# Input_stage.net
KiCad netlist of a schematic drawn in Altium Designer
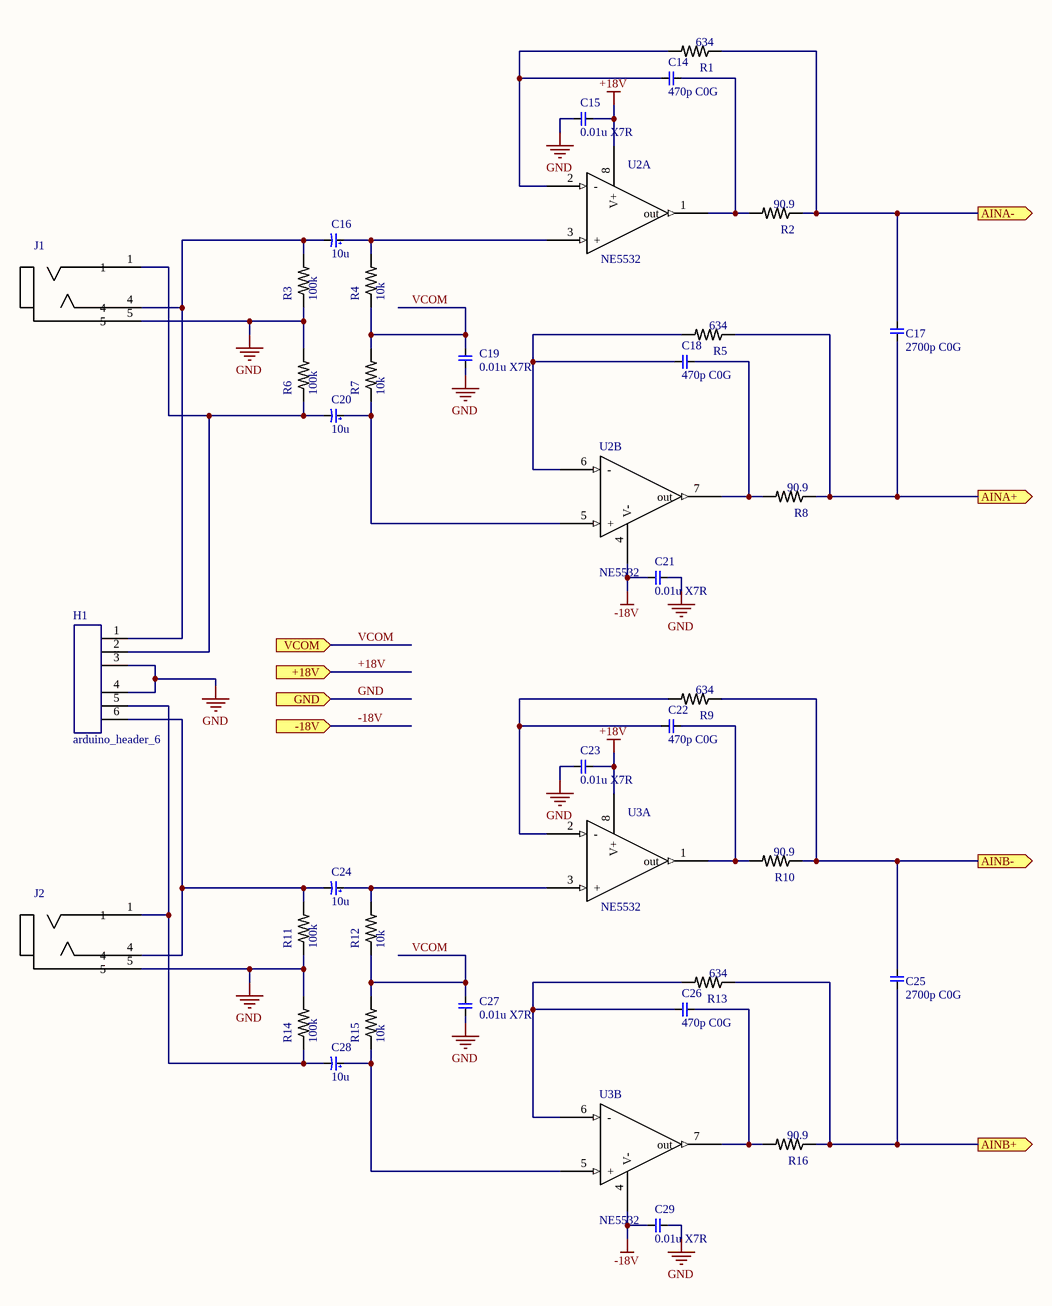
[diagram p0: Input_stage.SchDoc]

(export (version "E")
  (design (tool "Eeschema 10.0.6"))
  (components
    (comp (ref "C14") (value "470p C0G") (footprint "0805_cap") (libsource (lib "Codec_board") (part "Cap")))
    (comp (ref "C15") (value "0.01u X7R") (footprint "0805_cap") (libsource (lib "Codec_board") (part "Cap")))
    (comp (ref "C16")
      (value "10u")
      (footprint "cap 4x5.4")
      (libsource (lib "Codec_board") (part "Cap_electrolytic"))
    )
    (comp (ref "C17") (value "2700p C0G") (footprint "0805_cap") (libsource (lib "Codec_board") (part "Cap")))
    (comp (ref "C18") (value "470p C0G") (footprint "0805_cap") (libsource (lib "Codec_board") (part "Cap")))
    (comp (ref "C19") (value "0.01u X7R") (footprint "0805_cap") (libsource (lib "Codec_board") (part "Cap")))
    (comp (ref "C20")
      (value "10u")
      (footprint "cap 4x5.4")
      (libsource (lib "Codec_board") (part "Cap_electrolytic"))
    )
    (comp (ref "C21") (value "0.01u X7R") (footprint "0805_cap") (libsource (lib "Codec_board") (part "Cap")))
    (comp (ref "C22") (value "470p C0G") (footprint "0805_cap") (libsource (lib "Codec_board") (part "Cap")))
    (comp (ref "C23") (value "0.01u X7R") (footprint "0805_cap") (libsource (lib "Codec_board") (part "Cap")))
    (comp (ref "C24")
      (value "10u")
      (footprint "cap 4x5.4")
      (libsource (lib "Codec_board") (part "Cap_electrolytic"))
    )
    (comp (ref "C25") (value "2700p C0G") (footprint "0805_cap") (libsource (lib "Codec_board") (part "Cap")))
    (comp (ref "C26") (value "470p C0G") (footprint "0805_cap") (libsource (lib "Codec_board") (part "Cap")))
    (comp (ref "C27") (value "0.01u X7R") (footprint "0805_cap") (libsource (lib "Codec_board") (part "Cap")))
    (comp (ref "C28")
      (value "10u")
      (footprint "cap 4x5.4")
      (libsource (lib "Codec_board") (part "Cap_electrolytic"))
    )
    (comp (ref "C29") (value "0.01u X7R") (footprint "0805_cap") (libsource (lib "Codec_board") (part "Cap")))
    (comp (ref "H1")
      (value "arduino_header_6")
      (footprint "header-6_male")
      (libsource (lib "Codec_board") (part "arduino_header_6"))
    )
    (comp (ref "J1")
      (value "35RASMT2BHNTRX")
      (footprint "SWITCHCRAFT_35RASMT2BHNTRX")
      (description "Conn 3.5MM Stereo Jack F 3 POS Solder RA SMD 3 Terminal 1 Port T/R")
      (fields (field (name "MF") "Switchcraft"))
      (libsource (lib "Codec_board") (part "3.5mm jack stereo smd"))
    )
    (comp (ref "J2")
      (value "35RASMT2BHNTRX")
      (footprint "SWITCHCRAFT_35RASMT2BHNTRX")
      (description "Conn 3.5MM Stereo Jack F 3 POS Solder RA SMD 3 Terminal 1 Port T/R")
      (fields (field (name "MF") "Switchcraft"))
      (libsource (lib "Codec_board") (part "3.5mm jack stereo smd"))
    )
    (comp (ref "R1")
      (value "634")
      (footprint "0805")
      (description "RES SMD  1/8W 0805")
      (fields (field (name "MF") "Yageo") (field (name "MP") "AC0805JR-070RL"))
      (libsource (lib "Codec_board") (part "res my"))
    )
    (comp (ref "R2")
      (value "90.9")
      (footprint "0805")
      (description "RES SMD  1/8W 0805")
      (fields (field (name "MF") "Yageo") (field (name "MP") "AC0805JR-070RL"))
      (libsource (lib "Codec_board") (part "res my"))
    )
    (comp (ref "R3")
      (value "100k")
      (footprint "0805")
      (description "RES SMD  1/8W 0805")
      (fields (field (name "MF") "Yageo") (field (name "MP") "AC0805JR-070RL"))
      (libsource (lib "Codec_board") (part "res my"))
    )
    (comp (ref "R4")
      (value "10k")
      (footprint "0805")
      (description "RES SMD  1/8W 0805")
      (fields (field (name "MF") "Yageo") (field (name "MP") "AC0805JR-070RL"))
      (libsource (lib "Codec_board") (part "res my"))
    )
    (comp (ref "R5")
      (value "634")
      (footprint "0805")
      (description "RES SMD  1/8W 0805")
      (fields (field (name "MF") "Yageo") (field (name "MP") "AC0805JR-070RL"))
      (libsource (lib "Codec_board") (part "res my"))
    )
    (comp (ref "R6")
      (value "100k")
      (footprint "0805")
      (description "RES SMD  1/8W 0805")
      (fields (field (name "MF") "Yageo") (field (name "MP") "AC0805JR-070RL"))
      (libsource (lib "Codec_board") (part "res my"))
    )
    (comp (ref "R7")
      (value "10k")
      (footprint "0805")
      (description "RES SMD  1/8W 0805")
      (fields (field (name "MF") "Yageo") (field (name "MP") "AC0805JR-070RL"))
      (libsource (lib "Codec_board") (part "res my"))
    )
    (comp (ref "R8")
      (value "90.9")
      (footprint "0805")
      (description "RES SMD  1/8W 0805")
      (fields (field (name "MF") "Yageo") (field (name "MP") "AC0805JR-070RL"))
      (libsource (lib "Codec_board") (part "res my"))
    )
    (comp (ref "R9")
      (value "634")
      (footprint "0805")
      (description "RES SMD  1/8W 0805")
      (fields (field (name "MF") "Yageo") (field (name "MP") "AC0805JR-070RL"))
      (libsource (lib "Codec_board") (part "res my"))
    )
    (comp (ref "R10")
      (value "90.9")
      (footprint "0805")
      (description "RES SMD  1/8W 0805")
      (fields (field (name "MF") "Yageo") (field (name "MP") "AC0805JR-070RL"))
      (libsource (lib "Codec_board") (part "res my"))
    )
    (comp (ref "R11")
      (value "100k")
      (footprint "0805")
      (description "RES SMD  1/8W 0805")
      (fields (field (name "MF") "Yageo") (field (name "MP") "AC0805JR-070RL"))
      (libsource (lib "Codec_board") (part "res my"))
    )
    (comp (ref "R12")
      (value "10k")
      (footprint "0805")
      (description "RES SMD  1/8W 0805")
      (fields (field (name "MF") "Yageo") (field (name "MP") "AC0805JR-070RL"))
      (libsource (lib "Codec_board") (part "res my"))
    )
    (comp (ref "R13")
      (value "634")
      (footprint "0805")
      (description "RES SMD  1/8W 0805")
      (fields (field (name "MF") "Yageo") (field (name "MP") "AC0805JR-070RL"))
      (libsource (lib "Codec_board") (part "res my"))
    )
    (comp (ref "R14")
      (value "100k")
      (footprint "0805")
      (description "RES SMD  1/8W 0805")
      (fields (field (name "MF") "Yageo") (field (name "MP") "AC0805JR-070RL"))
      (libsource (lib "Codec_board") (part "res my"))
    )
    (comp (ref "R15")
      (value "10k")
      (footprint "0805")
      (description "RES SMD  1/8W 0805")
      (fields (field (name "MF") "Yageo") (field (name "MP") "AC0805JR-070RL"))
      (libsource (lib "Codec_board") (part "res my"))
    )
    (comp (ref "R16")
      (value "90.9")
      (footprint "0805")
      (description "RES SMD  1/8W 0805")
      (fields (field (name "MF") "Yageo") (field (name "MP") "AC0805JR-070RL"))
      (libsource (lib "Codec_board") (part "res my"))
    )
    (comp (ref "U2") (value "NE5532") (footprint "SOIC-8") (libsource (lib "Codec_board") (part "OPA2277")))
    (comp (ref "U3") (value "NE5532") (footprint "SOIC-8") (libsource (lib "Codec_board") (part "OPA2277")))
  )
  (nets
    (net (code "1") (name "+18V") (class "Default")
      (node (ref "C15") (pin "2") (pinfunction "2_2") (pintype "passive"))
      (node (ref "C23") (pin "2") (pinfunction "2_2") (pintype "passive"))
      (node (ref "U2") (pin "8") (pinfunction "V+_8") (pintype "passive"))
      (node (ref "U3") (pin "8") (pinfunction "V+_8") (pintype "passive"))
    )
    (net (code "2") (name "-18V") (class "Default")
      (node (ref "C21") (pin "2") (pinfunction "2_2") (pintype "passive"))
      (node (ref "C29") (pin "2") (pinfunction "2_2") (pintype "passive"))
      (node (ref "U2") (pin "4") (pinfunction "V-_4") (pintype "passive"))
      (node (ref "U3") (pin "4") (pinfunction "V-_4") (pintype "passive"))
    )
    (net (code "3") (name "/AINA+") (class "Default")
      (node (ref "C17") (pin "2") (pinfunction "2_2") (pintype "passive"))
      (node (ref "R5") (pin "1") (pinfunction "1_1") (pintype "passive"))
      (node (ref "R8") (pin "1") (pinfunction "1_1") (pintype "passive"))
    )
    (net (code "4") (name "/AINA-") (class "Default")
      (node (ref "C17") (pin "1") (pinfunction "1_1") (pintype "passive"))
      (node (ref "R1") (pin "1") (pinfunction "1_1") (pintype "passive"))
      (node (ref "R2") (pin "1") (pinfunction "1_1") (pintype "passive"))
    )
    (net (code "5") (name "/AINB+") (class "Default")
      (node (ref "C25") (pin "2") (pinfunction "2_2") (pintype "passive"))
      (node (ref "R13") (pin "1") (pinfunction "1_1") (pintype "passive"))
      (node (ref "R16") (pin "1") (pinfunction "1_1") (pintype "passive"))
    )
    (net (code "6") (name "/AINB-") (class "Default")
      (node (ref "C25") (pin "1") (pinfunction "1_1") (pintype "passive"))
      (node (ref "R10") (pin "1") (pinfunction "1_1") (pintype "passive"))
      (node (ref "R9") (pin "1") (pinfunction "1_1") (pintype "passive"))
    )
    (net (code "7") (name "/VCOM") (class "Default")
      (node (ref "C19") (pin "2") (pinfunction "2_2") (pintype "passive"))
      (node (ref "C27") (pin "2") (pinfunction "2_2") (pintype "passive"))
      (node (ref "R12") (pin "1") (pinfunction "1_1") (pintype "passive"))
      (node (ref "R15") (pin "2") (pinfunction "2_2") (pintype "passive"))
      (node (ref "R4") (pin "1") (pinfunction "1_1") (pintype "passive"))
      (node (ref "R7") (pin "2") (pinfunction "2_2") (pintype "passive"))
    )
    (net (code "8") (name "GND") (class "Default")
      (node (ref "C15") (pin "1") (pinfunction "1_1") (pintype "passive"))
      (node (ref "C19") (pin "1") (pinfunction "1_1") (pintype "passive"))
      (node (ref "C21") (pin "1") (pinfunction "1_1") (pintype "passive"))
      (node (ref "C23") (pin "1") (pinfunction "1_1") (pintype "passive"))
      (node (ref "C27") (pin "1") (pinfunction "1_1") (pintype "passive"))
      (node (ref "C29") (pin "1") (pinfunction "1_1") (pintype "passive"))
      (node (ref "H1") (pin "3") (pinfunction "3_3") (pintype "passive"))
      (node (ref "H1") (pin "4") (pinfunction "4_4") (pintype "passive"))
      (node (ref "J1") (pin "5") (pinfunction "5_5") (pintype "passive"))
      (node (ref "J2") (pin "5") (pinfunction "5_5") (pintype "passive"))
      (node (ref "R11") (pin "1") (pinfunction "1_1") (pintype "passive"))
      (node (ref "R14") (pin "2") (pinfunction "2_2") (pintype "passive"))
      (node (ref "R3") (pin "1") (pinfunction "1_1") (pintype "passive"))
      (node (ref "R6") (pin "2") (pinfunction "2_2") (pintype "passive"))
    )
    (net (code "9") (name "Net-(C16-Pad2)") (class "Default")
      (node (ref "C16") (pin "2") (pinfunction "2_2") (pintype "passive"))
      (node (ref "H1") (pin "1") (pinfunction "1_1") (pintype "passive"))
      (node (ref "J1") (pin "4") (pinfunction "4_4") (pintype "passive"))
      (node (ref "R3") (pin "2") (pinfunction "2_2") (pintype "passive"))
    )
    (net (code "10") (name "Net-(C20-Pad2)") (class "Default")
      (node (ref "C20") (pin "2") (pinfunction "2_2") (pintype "passive"))
      (node (ref "H1") (pin "2") (pinfunction "2_2") (pintype "passive"))
      (node (ref "J1") (pin "1") (pinfunction "1_1") (pintype "passive"))
      (node (ref "R6") (pin "1") (pinfunction "1_1") (pintype "passive"))
    )
    (net (code "11") (name "Net-(C24-Pad2)") (class "Default")
      (node (ref "C24") (pin "2") (pinfunction "2_2") (pintype "passive"))
      (node (ref "H1") (pin "6") (pinfunction "6_6") (pintype "passive"))
      (node (ref "J2") (pin "4") (pinfunction "4_4") (pintype "passive"))
      (node (ref "R11") (pin "2") (pinfunction "2_2") (pintype "passive"))
    )
    (net (code "12") (name "Net-(C28-Pad2)") (class "Default")
      (node (ref "C28") (pin "2") (pinfunction "2_2") (pintype "passive"))
      (node (ref "H1") (pin "5") (pinfunction "5_5") (pintype "passive"))
      (node (ref "J2") (pin "1") (pinfunction "1_1") (pintype "passive"))
      (node (ref "R14") (pin "1") (pinfunction "1_1") (pintype "passive"))
    )
    (net (code "13") (name "Net-(U2A-+)") (class "Default")
      (node (ref "C16") (pin "1") (pinfunction "1_1") (pintype "passive"))
      (node (ref "R4") (pin "2") (pinfunction "2_2") (pintype "passive"))
      (node (ref "U2") (pin "3") (pinfunction "+_3") (pintype "input"))
    )
    (net (code "14") (name "Net-(U2A--)") (class "Default")
      (node (ref "C14") (pin "2") (pinfunction "2_2") (pintype "passive"))
      (node (ref "R1") (pin "2") (pinfunction "2_2") (pintype "passive"))
      (node (ref "U2") (pin "2") (pinfunction "-_2") (pintype "input"))
    )
    (net (code "15") (name "Net-(U2A-out)") (class "Default")
      (node (ref "C14") (pin "1") (pinfunction "1_1") (pintype "passive"))
      (node (ref "R2") (pin "2") (pinfunction "2_2") (pintype "passive"))
      (node (ref "U2") (pin "1") (pinfunction "out_1") (pintype "output"))
    )
    (net (code "16") (name "Net-(U2B-+)") (class "Default")
      (node (ref "C20") (pin "1") (pinfunction "1_1") (pintype "passive"))
      (node (ref "R7") (pin "1") (pinfunction "1_1") (pintype "passive"))
      (node (ref "U2") (pin "5") (pinfunction "+_5") (pintype "input"))
    )
    (net (code "17") (name "Net-(U2B--)") (class "Default")
      (node (ref "C18") (pin "2") (pinfunction "2_2") (pintype "passive"))
      (node (ref "R5") (pin "2") (pinfunction "2_2") (pintype "passive"))
      (node (ref "U2") (pin "6") (pinfunction "-_6") (pintype "input"))
    )
    (net (code "18") (name "Net-(U2B-out)") (class "Default")
      (node (ref "C18") (pin "1") (pinfunction "1_1") (pintype "passive"))
      (node (ref "R8") (pin "2") (pinfunction "2_2") (pintype "passive"))
      (node (ref "U2") (pin "7") (pinfunction "out_7") (pintype "output"))
    )
    (net (code "19") (name "Net-(U3A-+)") (class "Default")
      (node (ref "C24") (pin "1") (pinfunction "1_1") (pintype "passive"))
      (node (ref "R12") (pin "2") (pinfunction "2_2") (pintype "passive"))
      (node (ref "U3") (pin "3") (pinfunction "+_3") (pintype "input"))
    )
    (net (code "20") (name "Net-(U3A--)") (class "Default")
      (node (ref "C22") (pin "2") (pinfunction "2_2") (pintype "passive"))
      (node (ref "R9") (pin "2") (pinfunction "2_2") (pintype "passive"))
      (node (ref "U3") (pin "2") (pinfunction "-_2") (pintype "input"))
    )
    (net (code "21") (name "Net-(U3A-out)") (class "Default")
      (node (ref "C22") (pin "1") (pinfunction "1_1") (pintype "passive"))
      (node (ref "R10") (pin "2") (pinfunction "2_2") (pintype "passive"))
      (node (ref "U3") (pin "1") (pinfunction "out_1") (pintype "output"))
    )
    (net (code "22") (name "Net-(U3B-+)") (class "Default")
      (node (ref "C28") (pin "1") (pinfunction "1_1") (pintype "passive"))
      (node (ref "R15") (pin "1") (pinfunction "1_1") (pintype "passive"))
      (node (ref "U3") (pin "5") (pinfunction "+_5") (pintype "input"))
    )
    (net (code "23") (name "Net-(U3B--)") (class "Default")
      (node (ref "C26") (pin "2") (pinfunction "2_2") (pintype "passive"))
      (node (ref "R13") (pin "2") (pinfunction "2_2") (pintype "passive"))
      (node (ref "U3") (pin "6") (pinfunction "-_6") (pintype "input"))
    )
    (net (code "24") (name "Net-(U3B-out)") (class "Default")
      (node (ref "C26") (pin "1") (pinfunction "1_1") (pintype "passive"))
      (node (ref "R16") (pin "2") (pinfunction "2_2") (pintype "passive"))
      (node (ref "U3") (pin "7") (pinfunction "out_7") (pintype "output"))
    )
  )
)
